# Wifi.net
KiCad netlist of a schematic drawn in Altium Designer
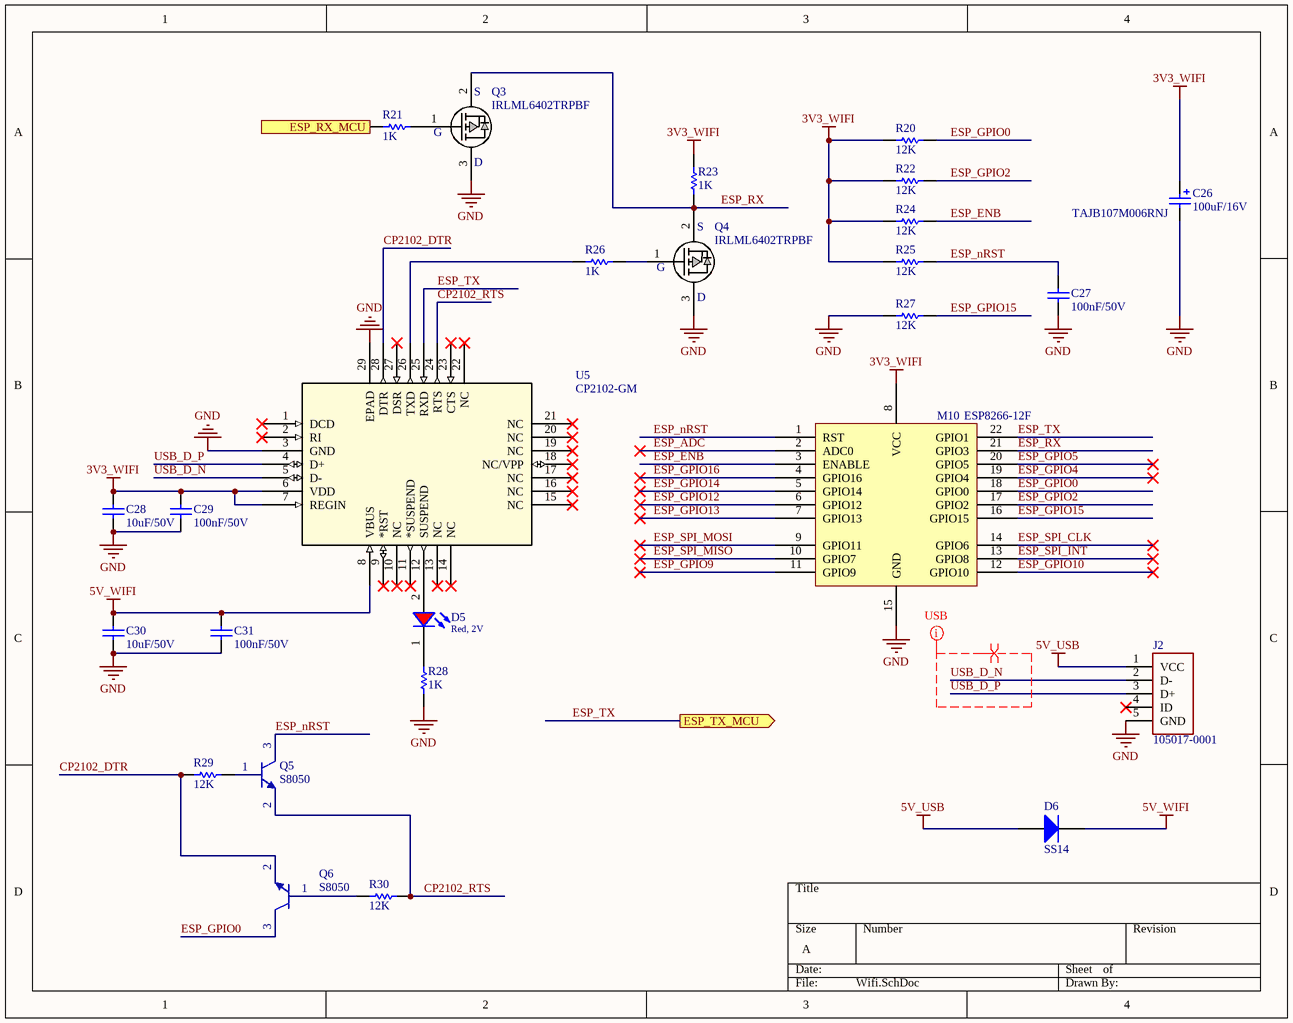
[diagram p0: Wifi.SchDoc]

(export (version "E")
  (design (tool "Eeschema 10.0.6"))
  (components
    (comp (ref "C26")
      (value "100uF/16V")
      (footprint "CAP_SM_TAN")
      (fields
        (field (name "MANUFACTURER") "Nichicon")
        (field (name "MANUFACTURER PART NUMBER") "UWX1C101MCL1GB")
        (field (name "Comment") "TAJB107M006RNJ")
      )
      (libsource (lib "Capacitor") (part "Cap-Tan-100uF-16V"))
    )
    (comp (ref "C27")
      (value "100nF/50V")
      (footprint "CAP-SM-0805")
      (description "CAP CER 0.1UF 50V Y5V 0805")
      (fields
        (field (name "MANUFACTURER") "Samsung Electro-Mechanics")
        (field (name "MANUFACTURER PART NUMBER") "CL21F104ZBCNNNC")
      )
      (libsource (lib "Capacitor") (part "Cap-100nF-50V-0805"))
    )
    (comp (ref "C28")
      (value "10uF/50V")
      (footprint "CAP-SM-0805")
      (description "CAP CER 10UF 50V X5R 0805")
      (fields
        (field (name "MANUFACTURER") "Yageo")
        (field (name "MANUFACTURER PART NUMBER") "CC0805KKX5R9BB106")
      )
      (libsource (lib "Capacitor") (part "Cap-10uF-50V-0805"))
    )
    (comp (ref "C29")
      (value "100nF/50V")
      (footprint "CAP-SM-0805")
      (description "CAP CER 0.1UF 50V Y5V 0805")
      (fields
        (field (name "MANUFACTURER") "Samsung Electro-Mechanics")
        (field (name "MANUFACTURER PART NUMBER") "CL21F104ZBCNNNC")
      )
      (libsource (lib "Capacitor") (part "Cap-100nF-50V-0805"))
    )
    (comp (ref "C30")
      (value "10uF/50V")
      (footprint "CAP-SM-0805")
      (description "CAP CER 10UF 50V X5R 0805")
      (fields
        (field (name "MANUFACTURER") "Yageo")
        (field (name "MANUFACTURER PART NUMBER") "CC0805KKX5R9BB106")
      )
      (libsource (lib "Capacitor") (part "Cap-10uF-50V-0805"))
    )
    (comp (ref "C31")
      (value "100nF/50V")
      (footprint "CAP-SM-0805")
      (description "CAP CER 0.1UF 50V Y5V 0805")
      (fields
        (field (name "MANUFACTURER") "Samsung Electro-Mechanics")
        (field (name "MANUFACTURER PART NUMBER") "CL21F104ZBCNNNC")
      )
      (libsource (lib "Capacitor") (part "Cap-100nF-50V-0805"))
    )
    (comp (ref "D5")
      (value "Red, 2V")
      (footprint "WL-SMCW_0805")
      (description "WL-SMCW SMT Mono-color Chip LED Waterclear, size 0805, Red, 2V, 140deg")
      (fields (field (name "PART NUMBER") "150080RS75000") (field (name "PUBLISHER") "Wurth Elektronik"))
      (libsource (lib "LED_150060BS75000_Altium_WL-SMCW_rev20a") (part "150080RS75000"))
    )
    (comp (ref "D6")
      (value "SS14")
      (footprint "SS14")
      (description "DIODE SCHOTTKY 40V 1A SMA")
      (fields (field (name "MANUFACTURER") "ON Semiconductor"))
      (libsource (lib "Diode") (part "Diode-SS14"))
    )
    (comp (ref "J2")
      (value "105017-0001")
      (footprint "CONN_105017-0001")
      (description "No Description Available")
      (fields (field (name "COPYRIGHT") "Copyright (C) 2018 Accelerated Designs. All rights reserved"))
      (libsource (lib "Header-connector") (part "105017-0001"))
    )
    (comp (ref "M10")
      (value "ESP8266-12F")
      (footprint "ESP8266-12F")
      (fields (field (name "LOCAL SUPPLIER LINK PART NUMBER") "HS000912"))
      (libsource (lib "PIFWRoBot") (part "ESP8266-12F"))
    )
    (comp (ref "Q3")
      (value "IRLML6402TRPBF")
      (footprint "SOT23_NEX")
      (description "P-Channel 20V 3.7A (Ta) 1.3W (Ta) Surface Mount Micro3™/SOT-23")
      (libsource (lib "MOSFET") (part "IRLML6402TRPBF"))
    )
    (comp (ref "Q4")
      (value "IRLML6402TRPBF")
      (footprint "SOT23_NEX")
      (description "P-Channel 20V 3.7A (Ta) 1.3W (Ta) Surface Mount Micro3™/SOT-23")
      (libsource (lib "MOSFET") (part "IRLML6402TRPBF"))
    )
    (comp (ref "Q5") (value "S8050") (footprint "SOT23_NEX") (libsource (lib "BJT") (part "S8050")))
    (comp (ref "Q6") (value "S8050") (footprint "SOT23_NEX") (libsource (lib "BJT") (part "S8050")))
    (comp (ref "R20")
      (value "12K")
      (footprint "Resistor:RES-SM-0805")
      (description "RES 12 KOHM JUMPER 0805")
      (fields
        (field (name "MANUFACTURER") "Vishay Thin Film")
        (field (name "MANUFACTURER PART NUMBER") "PAT0805E3121BST1")
      )
      (libsource (lib "Resistor") (part "Res-12K-0805"))
    )
    (comp (ref "R21")
      (value "1K")
      (footprint "Resistor:RES-SM-0805")
      (description "RES 1K OHM 1% 1/4W 0805")
      (fields
        (field (name "MANUFACTURER") "Stackpole Electronics Inc")
        (field (name "MANUFACTURER PART NUMBER") "RNCP0805FTD1K00")
      )
      (libsource (lib "Resistor") (part "Res-1K-0805"))
    )
    (comp (ref "R22")
      (value "12K")
      (footprint "Resistor:RES-SM-0805")
      (description "RES 12 KOHM JUMPER 0805")
      (fields
        (field (name "MANUFACTURER") "Vishay Thin Film")
        (field (name "MANUFACTURER PART NUMBER") "PAT0805E3121BST1")
      )
      (libsource (lib "Resistor") (part "Res-12K-0805"))
    )
    (comp (ref "R23")
      (value "1K")
      (footprint "Resistor:RES-SM-0805")
      (description "RES 1K OHM 1% 1/4W 0805")
      (fields
        (field (name "MANUFACTURER") "Stackpole Electronics Inc")
        (field (name "MANUFACTURER PART NUMBER") "RNCP0805FTD1K00")
      )
      (libsource (lib "Resistor") (part "Res-1K-0805"))
    )
    (comp (ref "R24")
      (value "12K")
      (footprint "Resistor:RES-SM-0805")
      (description "RES 12 KOHM JUMPER 0805")
      (fields
        (field (name "MANUFACTURER") "Vishay Thin Film")
        (field (name "MANUFACTURER PART NUMBER") "PAT0805E3121BST1")
      )
      (libsource (lib "Resistor") (part "Res-12K-0805"))
    )
    (comp (ref "R25")
      (value "12K")
      (footprint "Resistor:RES-SM-0805")
      (description "RES 12 KOHM JUMPER 0805")
      (fields
        (field (name "MANUFACTURER") "Vishay Thin Film")
        (field (name "MANUFACTURER PART NUMBER") "PAT0805E3121BST1")
      )
      (libsource (lib "Resistor") (part "Res-12K-0805"))
    )
    (comp (ref "R26")
      (value "1K")
      (footprint "Resistor:RES-SM-0805")
      (description "RES 1K OHM 1% 1/4W 0805")
      (fields
        (field (name "MANUFACTURER") "Stackpole Electronics Inc")
        (field (name "MANUFACTURER PART NUMBER") "RNCP0805FTD1K00")
      )
      (libsource (lib "Resistor") (part "Res-1K-0805"))
    )
    (comp (ref "R27")
      (value "12K")
      (footprint "Resistor:RES-SM-0805")
      (description "RES 12 KOHM JUMPER 0805")
      (fields
        (field (name "MANUFACTURER") "Vishay Thin Film")
        (field (name "MANUFACTURER PART NUMBER") "PAT0805E3121BST1")
      )
      (libsource (lib "Resistor") (part "Res-12K-0805"))
    )
    (comp (ref "R28")
      (value "1K")
      (footprint "Resistor:RES-SM-0805")
      (description "RES 1K OHM 1% 1/4W 0805")
      (fields
        (field (name "MANUFACTURER") "Stackpole Electronics Inc")
        (field (name "MANUFACTURER PART NUMBER") "RNCP0805FTD1K00")
      )
      (libsource (lib "Resistor") (part "Res-1K-0805"))
    )
    (comp (ref "R29")
      (value "12K")
      (footprint "Resistor:RES-SM-0805")
      (description "RES 12 KOHM JUMPER 0805")
      (fields
        (field (name "MANUFACTURER") "Vishay Thin Film")
        (field (name "MANUFACTURER PART NUMBER") "PAT0805E3121BST1")
      )
      (libsource (lib "Resistor") (part "Res-12K-0805"))
    )
    (comp (ref "R30")
      (value "12K")
      (footprint "Resistor:RES-SM-0805")
      (description "RES 12 KOHM JUMPER 0805")
      (fields
        (field (name "MANUFACTURER") "Vishay Thin Film")
        (field (name "MANUFACTURER PART NUMBER") "PAT0805E3121BST1")
      )
      (libsource (lib "Resistor") (part "Res-12K-0805"))
    )
    (comp (ref "U5")
      (value "CP2102-GM")
      (footprint "CP2102-GM")
      (fields (field (name "COPYRIGHT") "Copyright (C) 2018 Accelerated Designs. All rights reserved"))
      (libsource (lib "PIFWRoBot") (part "CP2102-GM"))
    )
  )
  (nets
    (net (code "1") (name "/CP2102_DTR") (class "Default")
      (node (ref "Q6") (pin "2") (pinfunction "E_2") (pintype "passive"))
      (node (ref "R29") (pin "1") (pinfunction "1_1") (pintype "passive"))
      (node (ref "U5") (pin "28") (pinfunction "DTR_28") (pintype "output"))
    )
    (net (code "2") (name "/CP2102_RTS") (class "Default")
      (node (ref "Q5") (pin "2") (pinfunction "E_2") (pintype "passive"))
      (node (ref "R30") (pin "2") (pinfunction "2_2") (pintype "passive"))
      (node (ref "U5") (pin "24") (pinfunction "RTS_24") (pintype "output"))
    )
    (net (code "3") (name "/ESP_ADC") (class "Default")
      (node (ref "M10") (pin "2") (pinfunction "ADC0_2") (pintype "passive+no_connect"))
    )
    (net (code "4") (name "/ESP_ENB") (class "Default")
      (node (ref "M10") (pin "3") (pinfunction "ENABLE_3") (pintype "passive"))
      (node (ref "R24") (pin "2") (pinfunction "2_2") (pintype "passive"))
    )
    (net (code "5") (name "/ESP_GPIO0") (class "Default")
      (node (ref "M10") (pin "18") (pinfunction "GPIO0_18") (pintype "passive"))
      (node (ref "Q6") (pin "3") (pinfunction "C_3") (pintype "passive"))
      (node (ref "R20") (pin "2") (pinfunction "2_2") (pintype "passive"))
    )
    (net (code "6") (name "/ESP_GPIO2") (class "Default")
      (node (ref "M10") (pin "17") (pinfunction "GPIO2_17") (pintype "passive"))
      (node (ref "R22") (pin "2") (pinfunction "2_2") (pintype "passive"))
    )
    (net (code "7") (name "/ESP_GPIO4") (class "Default")
      (node (ref "M10") (pin "19") (pinfunction "GPIO4_19") (pintype "passive+no_connect"))
    )
    (net (code "8") (name "/ESP_GPIO5") (class "Default")
      (node (ref "M10") (pin "20") (pinfunction "GPIO5_20") (pintype "passive+no_connect"))
    )
    (net (code "9") (name "/ESP_GPIO9") (class "Default")
      (node (ref "M10") (pin "11") (pinfunction "GPIO9_11") (pintype "passive+no_connect"))
    )
    (net (code "10") (name "/ESP_GPIO10") (class "Default")
      (node (ref "M10") (pin "12") (pinfunction "GPIO10_12") (pintype "passive+no_connect"))
    )
    (net (code "11") (name "/ESP_GPIO12") (class "Default")
      (node (ref "M10") (pin "6") (pinfunction "GPIO12_6") (pintype "passive+no_connect"))
    )
    (net (code "12") (name "/ESP_GPIO13") (class "Default")
      (node (ref "M10") (pin "7") (pinfunction "GPIO13_7") (pintype "passive+no_connect"))
    )
    (net (code "13") (name "/ESP_GPIO14") (class "Default")
      (node (ref "M10") (pin "5") (pinfunction "GPIO14_5") (pintype "passive+no_connect"))
    )
    (net (code "14") (name "/ESP_GPIO15") (class "Default")
      (node (ref "M10") (pin "16") (pinfunction "GPIO15_16") (pintype "passive"))
      (node (ref "R27") (pin "2") (pinfunction "2_2") (pintype "passive"))
    )
    (net (code "15") (name "/ESP_GPIO16") (class "Default")
      (node (ref "M10") (pin "4") (pinfunction "GPIO16_4") (pintype "passive+no_connect"))
    )
    (net (code "16") (name "/ESP_RX") (class "Default")
      (node (ref "M10") (pin "21") (pinfunction "GPIO3_21") (pintype "passive"))
      (node (ref "Q3") (pin "2") (pinfunction "S_2") (pintype "passive"))
      (node (ref "Q4") (pin "2") (pinfunction "S_2") (pintype "passive"))
      (node (ref "R23") (pin "1") (pinfunction "1_1") (pintype "passive"))
    )
    (net (code "17") (name "/ESP_RX_MCU") (class "Default")
      (node (ref "R21") (pin "1") (pinfunction "1_1") (pintype "passive"))
    )
    (net (code "18") (name "/ESP_SPI_CLK") (class "Default")
      (node (ref "M10") (pin "14") (pinfunction "GPIO6_14") (pintype "passive+no_connect"))
    )
    (net (code "19") (name "/ESP_SPI_INT") (class "Default")
      (node (ref "M10") (pin "13") (pinfunction "GPIO8_13") (pintype "passive+no_connect"))
    )
    (net (code "20") (name "/ESP_SPI_MISO") (class "Default")
      (node (ref "M10") (pin "10") (pinfunction "GPIO7_10") (pintype "passive+no_connect"))
    )
    (net (code "21") (name "/ESP_SPI_MOSI") (class "Default")
      (node (ref "M10") (pin "9") (pinfunction "GPIO11_9") (pintype "passive+no_connect"))
    )
    (net (code "22") (name "/ESP_TX") (class "Default")
      (node (ref "M10") (pin "22") (pinfunction "GPIO1_22") (pintype "passive"))
      (node (ref "U5") (pin "25") (pinfunction "RXD_25") (pintype "input"))
    )
    (net (code "23") (name "/ESP_nRST") (class "Default")
      (node (ref "C27") (pin "2") (pinfunction "2_2") (pintype "passive"))
      (node (ref "M10") (pin "1") (pinfunction "RST_1") (pintype "passive"))
      (node (ref "Q5") (pin "3") (pinfunction "C_3") (pintype "passive"))
      (node (ref "R25") (pin "2") (pinfunction "2_2") (pintype "passive"))
    )
    (net (code "24") (name "/USB_D_N") (class "Default")
      (node (ref "J2") (pin "2") (pinfunction "D-_2") (pintype "passive"))
      (node (ref "U5") (pin "5") (pinfunction "D-_5") (pintype "bidirectional"))
    )
    (net (code "25") (name "/USB_D_P") (class "Default")
      (node (ref "J2") (pin "3") (pinfunction "D+_3") (pintype "passive"))
      (node (ref "U5") (pin "4") (pinfunction "D+_4") (pintype "bidirectional"))
    )
    (net (code "26") (name "3V3_WIFI") (class "Default")
      (node (ref "C26") (pin "1") (pinfunction "1_1") (pintype "passive"))
      (node (ref "C28") (pin "1") (pinfunction "1_1") (pintype "passive"))
      (node (ref "C29") (pin "2") (pinfunction "2_2") (pintype "passive"))
      (node (ref "M10") (pin "8") (pinfunction "VCC_8") (pintype "passive"))
      (node (ref "R20") (pin "1") (pinfunction "1_1") (pintype "passive"))
      (node (ref "R22") (pin "1") (pinfunction "1_1") (pintype "passive"))
      (node (ref "R23") (pin "2") (pinfunction "2_2") (pintype "passive"))
      (node (ref "R24") (pin "1") (pinfunction "1_1") (pintype "passive"))
      (node (ref "R25") (pin "1") (pinfunction "1_1") (pintype "passive"))
      (node (ref "U5") (pin "6") (pinfunction "VDD_6") (pintype "power_in"))
      (node (ref "U5") (pin "7") (pinfunction "REGIN_7") (pintype "input"))
    )
    (net (code "27") (name "5V_USB") (class "Default")
      (node (ref "D6") (pin "2") (pinfunction "A_2") (pintype "passive"))
      (node (ref "J2") (pin "1") (pinfunction "VCC_1") (pintype "passive"))
    )
    (net (code "28") (name "5V_WIFI") (class "Default")
      (node (ref "C30") (pin "2") (pinfunction "2_2") (pintype "passive"))
      (node (ref "C31") (pin "2") (pinfunction "2_2") (pintype "passive"))
      (node (ref "D6") (pin "1") (pinfunction "K_1") (pintype "passive"))
      (node (ref "U5") (pin "8") (pinfunction "VBUS_8") (pintype "input"))
    )
    (net (code "29") (name "GND") (class "Default")
      (node (ref "C26") (pin "2") (pinfunction "2_2") (pintype "passive"))
      (node (ref "C27") (pin "1") (pinfunction "1_1") (pintype "passive"))
      (node (ref "C28") (pin "2") (pinfunction "2_2") (pintype "passive"))
      (node (ref "C29") (pin "1") (pinfunction "1_1") (pintype "passive"))
      (node (ref "C30") (pin "1") (pinfunction "1_1") (pintype "passive"))
      (node (ref "C31") (pin "1") (pinfunction "1_1") (pintype "passive"))
      (node (ref "J2") (pin "5") (pinfunction "GND_5") (pintype "passive"))
      (node (ref "M10") (pin "15") (pinfunction "GND_15") (pintype "passive"))
      (node (ref "Q3") (pin "3") (pinfunction "D_3") (pintype "passive"))
      (node (ref "Q4") (pin "3") (pinfunction "D_3") (pintype "passive"))
      (node (ref "R27") (pin "1") (pinfunction "1_1") (pintype "passive"))
      (node (ref "R28") (pin "1") (pinfunction "1_1") (pintype "passive"))
      (node (ref "U5") (pin "29") (pinfunction "EPAD_29") (pintype "passive"))
      (node (ref "U5") (pin "3") (pinfunction "GND_3") (pintype "power_in"))
    )
    (net (code "30") (name "Net-(D5-A)") (class "Default")
      (node (ref "D5") (pin "2") (pinfunction "A_2") (pintype "passive"))
      (node (ref "U5") (pin "12") (pinfunction "SUSPEND_12") (pintype "output"))
    )
    (net (code "31") (name "Net-(D5-K)") (class "Default")
      (node (ref "D5") (pin "1") (pinfunction "K_1") (pintype "passive"))
      (node (ref "R28") (pin "2") (pinfunction "2_2") (pintype "passive"))
    )
    (net (code "32") (name "Net-(Q3-G)") (class "Default")
      (node (ref "Q3") (pin "1") (pinfunction "G_1") (pintype "passive"))
      (node (ref "R21") (pin "2") (pinfunction "2_2") (pintype "passive"))
    )
    (net (code "33") (name "Net-(Q4-G)") (class "Default")
      (node (ref "Q4") (pin "1") (pinfunction "G_1") (pintype "passive"))
      (node (ref "R26") (pin "1") (pinfunction "1_1") (pintype "passive"))
    )
    (net (code "34") (name "Net-(Q5-B)") (class "Default")
      (node (ref "Q5") (pin "1") (pinfunction "B_1") (pintype "passive"))
      (node (ref "R29") (pin "2") (pinfunction "2_2") (pintype "passive"))
    )
    (net (code "35") (name "Net-(Q6-B)") (class "Default")
      (node (ref "Q6") (pin "1") (pinfunction "B_1") (pintype "passive"))
      (node (ref "R30") (pin "1") (pinfunction "1_1") (pintype "passive"))
    )
    (net (code "36") (name "Net-(U5-TXD)") (class "Default")
      (node (ref "R26") (pin "2") (pinfunction "2_2") (pintype "passive"))
      (node (ref "U5") (pin "26") (pinfunction "TXD_26") (pintype "output"))
    )
    (net (code "37") (name "unconnected-(J2-ID-Pad4)") (class "Default")
      (node (ref "J2") (pin "4") (pinfunction "ID_4") (pintype "passive+no_connect"))
    )
    (net (code "38") (name "unconnected-(U5-*RST-Pad9)") (class "Default")
      (node (ref "U5") (pin "9") (pinfunction "*RST_9") (pintype "bidirectional+no_connect"))
    )
    (net (code "39") (name "unconnected-(U5-*SUSPEND-Pad11)") (class "Default")
      (node (ref "U5") (pin "11") (pinfunction "*SUSPEND_11") (pintype "output+no_connect"))
    )
    (net (code "40") (name "unconnected-(U5-CTS-Pad23)") (class "Default")
      (node (ref "U5") (pin "23") (pinfunction "CTS_23") (pintype "input+no_connect"))
    )
    (net (code "41") (name "unconnected-(U5-DCD-Pad1)") (class "Default")
      (node (ref "U5") (pin "1") (pinfunction "DCD_1") (pintype "input+no_connect"))
    )
    (net (code "42") (name "unconnected-(U5-DSR-Pad27)") (class "Default")
      (node (ref "U5") (pin "27") (pinfunction "DSR_27") (pintype "input+no_connect"))
    )
    (net (code "43") (name "unconnected-(U5-NC-Pad10)") (class "Default")
      (node (ref "U5") (pin "10") (pinfunction "NC_10") (pintype "passive+no_connect"))
    )
    (net (code "44") (name "unconnected-(U5-NC-Pad13)") (class "Default")
      (node (ref "U5") (pin "13") (pinfunction "NC_13") (pintype "passive+no_connect"))
    )
    (net (code "45") (name "unconnected-(U5-NC-Pad14)") (class "Default")
      (node (ref "U5") (pin "14") (pinfunction "NC_14") (pintype "passive+no_connect"))
    )
    (net (code "46") (name "unconnected-(U5-NC-Pad15)") (class "Default")
      (node (ref "U5") (pin "15") (pinfunction "NC_15") (pintype "passive+no_connect"))
    )
    (net (code "47") (name "unconnected-(U5-NC-Pad16)") (class "Default")
      (node (ref "U5") (pin "16") (pinfunction "NC_16") (pintype "passive+no_connect"))
    )
    (net (code "48") (name "unconnected-(U5-NC-Pad17)") (class "Default")
      (node (ref "U5") (pin "17") (pinfunction "NC_17") (pintype "passive+no_connect"))
    )
    (net (code "49") (name "unconnected-(U5-NC-Pad19)") (class "Default")
      (node (ref "U5") (pin "19") (pinfunction "NC_19") (pintype "passive+no_connect"))
    )
    (net (code "50") (name "unconnected-(U5-NC-Pad20)") (class "Default")
      (node (ref "U5") (pin "20") (pinfunction "NC_20") (pintype "passive+no_connect"))
    )
    (net (code "51") (name "unconnected-(U5-NC-Pad21)") (class "Default")
      (node (ref "U5") (pin "21") (pinfunction "NC_21") (pintype "passive+no_connect"))
    )
    (net (code "52") (name "unconnected-(U5-NC-Pad22)") (class "Default")
      (node (ref "U5") (pin "22") (pinfunction "NC_22") (pintype "passive+no_connect"))
    )
    (net (code "53") (name "unconnected-(U5-NC{slash}VPP-Pad18)") (class "Default")
      (node (ref "U5") (pin "18") (pinfunction "NC/VPP_18") (pintype "bidirectional+no_connect"))
    )
    (net (code "54") (name "unconnected-(U5-RI-Pad2)") (class "Default")
      (node (ref "U5") (pin "2") (pinfunction "RI_2") (pintype "input+no_connect"))
    )
  )
)
